# 4_0__TK040_31pin.net
KiCad netlist of a schematic drawn in Altium Designer
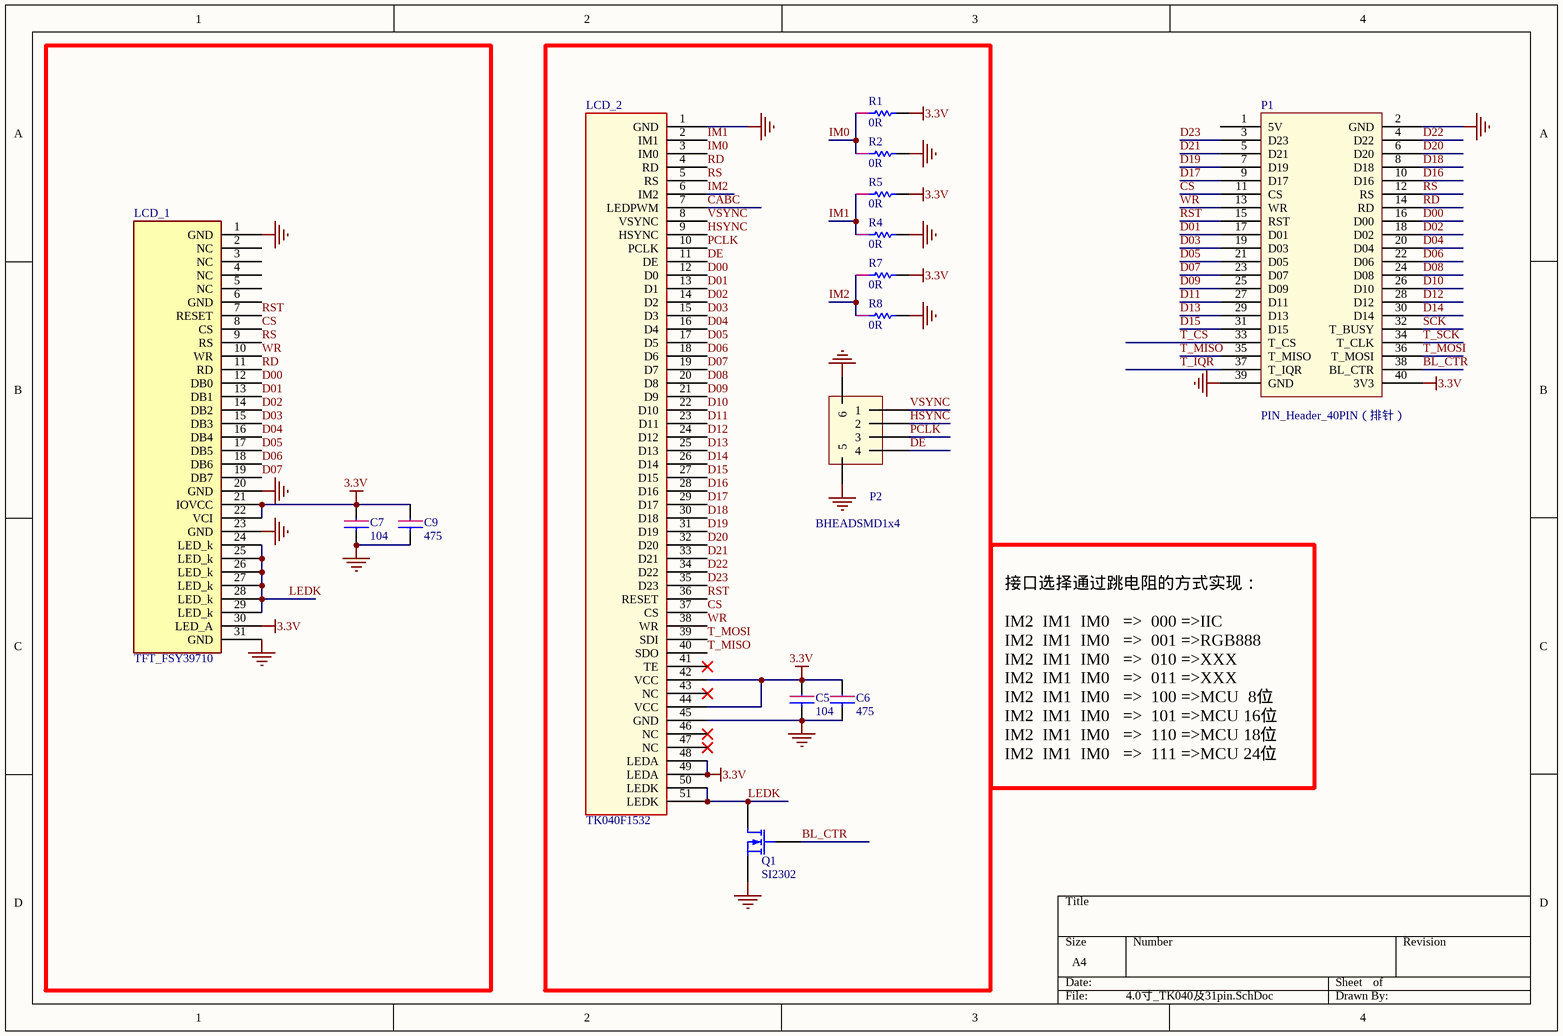
[diagram p0: 4.0寸_TK040及31pin.SchDoc]

(export (version "E")
  (design (tool "Eeschema 10.0.6"))
  (components
    (comp (ref "C5") (value "104") (footprint "C0603-1") (libsource (lib "Tiky") (part "cap")))
    (comp (ref "C6") (value "475") (footprint "C0603-2") (libsource (lib "Tiky") (part "cap")))
    (comp (ref "C7") (value "104") (footprint "C0603-1") (libsource (lib "Tiky") (part "cap")))
    (comp (ref "C9") (value "475") (footprint "C0603-1") (libsource (lib "Tiky") (part "cap")))
    (comp (ref "LCD_1")
      (value "TFT_FSY39710")
      (footprint "TFT_FSY39710")
      (libsource (lib "Tiky") (part "TFT_FSY39710"))
    )
    (comp (ref "LCD_2")
      (value "TK040F1532")
      (footprint "TK040F1532")
      (libsource (lib "Tiky") (part "TK040F1532"))
    )
    (comp (ref "P1")
      (value "PIN_Header_40PIN（排针）")
      (footprint "P_Head_2x20")
      (libsource (lib "Tiky") (part "PIN_Header_40PIN"))
    )
    (comp (ref "P2")
      (value "BHEADSMD1x4")
      (footprint "BHEADSMD1x4")
      (libsource (lib "Tiky") (part "BHEADSMD1x4"))
    )
    (comp (ref "Q1") (value "SI2302") (footprint "SOT23A") (libsource (lib "Tiky") (part "MOSFET-N")))
    (comp (ref "R1") (value "0R") (footprint "R0603") (libsource (lib "Tiky") (part "Resistor")))
    (comp (ref "R2") (value "0R") (footprint "R0603") (libsource (lib "Tiky") (part "Resistor")))
    (comp (ref "R4") (value "0R") (footprint "R0603") (libsource (lib "Tiky") (part "Resistor")))
    (comp (ref "R5") (value "0R") (footprint "R0603") (libsource (lib "Tiky") (part "Resistor")))
    (comp (ref "R7") (value "0R") (footprint "R0603") (libsource (lib "Tiky") (part "Resistor")))
    (comp (ref "R8") (value "0R") (footprint "R0603") (libsource (lib "Tiky") (part "Resistor")))
  )
  (nets
    (net (code "1") (name "/BL_CTR") (class "Default")
      (node (ref "P1") (pin "38") (pinfunction "BL_CTR_38") (pintype "passive"))
      (node (ref "Q1") (pin "1") (pinfunction "G_1") (pintype "passive"))
    )
    (net (code "2") (name "/CABC") (class "Default")
      (node (ref "LCD_2") (pin "7") (pinfunction "LEDPWM_7") (pintype "passive"))
    )
    (net (code "3") (name "/CS") (class "Default")
      (node (ref "LCD_1") (pin "8") (pinfunction "CS_8") (pintype "passive"))
      (node (ref "LCD_2") (pin "37") (pinfunction "CS_37") (pintype "passive"))
      (node (ref "P1") (pin "11") (pinfunction "CS_11") (pintype "passive"))
    )
    (net (code "4") (name "/D00") (class "Default")
      (node (ref "LCD_1") (pin "12") (pinfunction "DB0_12") (pintype "passive"))
      (node (ref "LCD_2") (pin "12") (pinfunction "D0_12") (pintype "passive"))
      (node (ref "P1") (pin "16") (pinfunction "D00_16") (pintype "passive"))
    )
    (net (code "5") (name "/D01") (class "Default")
      (node (ref "LCD_1") (pin "13") (pinfunction "DB1_13") (pintype "passive"))
      (node (ref "LCD_2") (pin "13") (pinfunction "D1_13") (pintype "passive"))
      (node (ref "P1") (pin "17") (pinfunction "D01_17") (pintype "passive"))
    )
    (net (code "6") (name "/D02") (class "Default")
      (node (ref "LCD_1") (pin "14") (pinfunction "DB2_14") (pintype "passive"))
      (node (ref "LCD_2") (pin "14") (pinfunction "D2_14") (pintype "passive"))
      (node (ref "P1") (pin "18") (pinfunction "D02_18") (pintype "passive"))
    )
    (net (code "7") (name "/D03") (class "Default")
      (node (ref "LCD_1") (pin "15") (pinfunction "DB3_15") (pintype "passive"))
      (node (ref "LCD_2") (pin "15") (pinfunction "D3_15") (pintype "passive"))
      (node (ref "P1") (pin "19") (pinfunction "D03_19") (pintype "passive"))
    )
    (net (code "8") (name "/D04") (class "Default")
      (node (ref "LCD_1") (pin "16") (pinfunction "DB4_16") (pintype "passive"))
      (node (ref "LCD_2") (pin "16") (pinfunction "D4_16") (pintype "passive"))
      (node (ref "P1") (pin "20") (pinfunction "D04_20") (pintype "passive"))
    )
    (net (code "9") (name "/D05") (class "Default")
      (node (ref "LCD_1") (pin "17") (pinfunction "DB5_17") (pintype "passive"))
      (node (ref "LCD_2") (pin "17") (pinfunction "D5_17") (pintype "passive"))
      (node (ref "P1") (pin "21") (pinfunction "D05_21") (pintype "passive"))
    )
    (net (code "10") (name "/D06") (class "Default")
      (node (ref "LCD_1") (pin "18") (pinfunction "DB6_18") (pintype "passive"))
      (node (ref "LCD_2") (pin "18") (pinfunction "D6_18") (pintype "passive"))
      (node (ref "P1") (pin "22") (pinfunction "D06_22") (pintype "passive"))
    )
    (net (code "11") (name "/D07") (class "Default")
      (node (ref "LCD_1") (pin "19") (pinfunction "DB7_19") (pintype "passive"))
      (node (ref "LCD_2") (pin "19") (pinfunction "D7_19") (pintype "passive"))
      (node (ref "P1") (pin "23") (pinfunction "D07_23") (pintype "passive"))
    )
    (net (code "12") (name "/D08") (class "Default")
      (node (ref "LCD_2") (pin "20") (pinfunction "D8_20") (pintype "passive"))
      (node (ref "P1") (pin "24") (pinfunction "D08_24") (pintype "passive"))
    )
    (net (code "13") (name "/D09") (class "Default")
      (node (ref "LCD_2") (pin "21") (pinfunction "D9_21") (pintype "passive"))
      (node (ref "P1") (pin "25") (pinfunction "D09_25") (pintype "passive"))
    )
    (net (code "14") (name "/D10") (class "Default")
      (node (ref "LCD_2") (pin "22") (pinfunction "D10_22") (pintype "passive"))
      (node (ref "P1") (pin "26") (pinfunction "D10_26") (pintype "passive"))
    )
    (net (code "15") (name "/D11") (class "Default")
      (node (ref "LCD_2") (pin "23") (pinfunction "D11_23") (pintype "passive"))
      (node (ref "P1") (pin "27") (pinfunction "D11_27") (pintype "passive"))
    )
    (net (code "16") (name "/D12") (class "Default")
      (node (ref "LCD_2") (pin "24") (pinfunction "D12_24") (pintype "passive"))
      (node (ref "P1") (pin "28") (pinfunction "D12_28") (pintype "passive"))
    )
    (net (code "17") (name "/D13") (class "Default")
      (node (ref "LCD_2") (pin "25") (pinfunction "D13_25") (pintype "passive"))
      (node (ref "P1") (pin "29") (pinfunction "D13_29") (pintype "passive"))
    )
    (net (code "18") (name "/D14") (class "Default")
      (node (ref "LCD_2") (pin "26") (pinfunction "D14_26") (pintype "passive"))
      (node (ref "P1") (pin "30") (pinfunction "D14_30") (pintype "passive"))
    )
    (net (code "19") (name "/D15") (class "Default")
      (node (ref "LCD_2") (pin "27") (pinfunction "D15_27") (pintype "passive"))
      (node (ref "P1") (pin "31") (pinfunction "D15_31") (pintype "passive"))
    )
    (net (code "20") (name "/D16") (class "Default")
      (node (ref "LCD_2") (pin "28") (pinfunction "D16_28") (pintype "passive"))
      (node (ref "P1") (pin "10") (pinfunction "D16_10") (pintype "passive"))
    )
    (net (code "21") (name "/D17") (class "Default")
      (node (ref "LCD_2") (pin "29") (pinfunction "D17_29") (pintype "passive"))
      (node (ref "P1") (pin "9") (pinfunction "D17_9") (pintype "passive"))
    )
    (net (code "22") (name "/D18") (class "Default")
      (node (ref "LCD_2") (pin "30") (pinfunction "D18_30") (pintype "passive"))
      (node (ref "P1") (pin "8") (pinfunction "D18_8") (pintype "passive"))
    )
    (net (code "23") (name "/D19") (class "Default")
      (node (ref "LCD_2") (pin "31") (pinfunction "D19_31") (pintype "passive"))
      (node (ref "P1") (pin "7") (pinfunction "D19_7") (pintype "passive"))
    )
    (net (code "24") (name "/D20") (class "Default")
      (node (ref "LCD_2") (pin "32") (pinfunction "D20_32") (pintype "passive"))
      (node (ref "P1") (pin "6") (pinfunction "D20_6") (pintype "passive"))
    )
    (net (code "25") (name "/D21") (class "Default")
      (node (ref "LCD_2") (pin "33") (pinfunction "D21_33") (pintype "passive"))
      (node (ref "P1") (pin "5") (pinfunction "D21_5") (pintype "passive"))
    )
    (net (code "26") (name "/D22") (class "Default")
      (node (ref "LCD_2") (pin "34") (pinfunction "D22_34") (pintype "passive"))
      (node (ref "P1") (pin "4") (pinfunction "D22_4") (pintype "passive"))
    )
    (net (code "27") (name "/D23") (class "Default")
      (node (ref "LCD_2") (pin "35") (pinfunction "D23_35") (pintype "passive"))
      (node (ref "P1") (pin "3") (pinfunction "D23_3") (pintype "passive"))
    )
    (net (code "28") (name "/DE") (class "Default")
      (node (ref "LCD_2") (pin "11") (pinfunction "DE_11") (pintype "passive"))
      (node (ref "P2") (pin "4") (pinfunction "4_4") (pintype "passive"))
    )
    (net (code "29") (name "/HSYNC") (class "Default")
      (node (ref "LCD_2") (pin "9") (pinfunction "HSYNC_9") (pintype "passive"))
      (node (ref "P2") (pin "2") (pinfunction "2_2") (pintype "passive"))
    )
    (net (code "30") (name "/IM0") (class "Default")
      (node (ref "LCD_2") (pin "3") (pinfunction "IM0_3") (pintype "passive"))
      (node (ref "R1") (pin "1") (pinfunction "1_1") (pintype "passive"))
      (node (ref "R2") (pin "1") (pinfunction "1_1") (pintype "passive"))
    )
    (net (code "31") (name "/IM1") (class "Default")
      (node (ref "LCD_2") (pin "2") (pinfunction "IM1_2") (pintype "passive"))
      (node (ref "R4") (pin "1") (pinfunction "1_1") (pintype "passive"))
      (node (ref "R5") (pin "1") (pinfunction "1_1") (pintype "passive"))
    )
    (net (code "32") (name "/IM2") (class "Default")
      (node (ref "LCD_2") (pin "6") (pinfunction "IM2_6") (pintype "passive"))
      (node (ref "R7") (pin "1") (pinfunction "1_1") (pintype "passive"))
      (node (ref "R8") (pin "1") (pinfunction "1_1") (pintype "passive"))
    )
    (net (code "33") (name "/LEDK") (class "Default")
      (node (ref "LCD_1") (pin "24") (pinfunction "LED_k_24") (pintype "passive"))
      (node (ref "LCD_1") (pin "25") (pinfunction "LED_k_25") (pintype "passive"))
      (node (ref "LCD_1") (pin "26") (pinfunction "LED_k_26") (pintype "passive"))
      (node (ref "LCD_1") (pin "27") (pinfunction "LED_k_27") (pintype "passive"))
      (node (ref "LCD_1") (pin "28") (pinfunction "LED_k_28") (pintype "passive"))
      (node (ref "LCD_1") (pin "29") (pinfunction "LED_k_29") (pintype "passive"))
      (node (ref "LCD_2") (pin "50") (pinfunction "LEDK_50") (pintype "passive"))
      (node (ref "LCD_2") (pin "51") (pinfunction "LEDK_51") (pintype "passive"))
      (node (ref "Q1") (pin "3") (pinfunction "D_3") (pintype "passive"))
    )
    (net (code "34") (name "/PCLK") (class "Default")
      (node (ref "LCD_2") (pin "10") (pinfunction "PCLK_10") (pintype "passive"))
      (node (ref "P2") (pin "3") (pinfunction "3_3") (pintype "passive"))
    )
    (net (code "35") (name "/RD") (class "Default")
      (node (ref "LCD_1") (pin "11") (pinfunction "RD_11") (pintype "passive"))
      (node (ref "LCD_2") (pin "4") (pinfunction "RD_4") (pintype "passive"))
      (node (ref "P1") (pin "14") (pinfunction "RD_14") (pintype "passive"))
    )
    (net (code "36") (name "/RS") (class "Default")
      (node (ref "LCD_1") (pin "9") (pinfunction "RS_9") (pintype "passive"))
      (node (ref "LCD_2") (pin "5") (pinfunction "RS_5") (pintype "passive"))
      (node (ref "P1") (pin "12") (pinfunction "RS_12") (pintype "passive"))
    )
    (net (code "37") (name "/RST") (class "Default")
      (node (ref "LCD_1") (pin "7") (pinfunction "RESET_7") (pintype "passive"))
      (node (ref "LCD_2") (pin "36") (pinfunction "RESET_36") (pintype "passive"))
      (node (ref "P1") (pin "15") (pinfunction "RST_15") (pintype "passive"))
    )
    (net (code "38") (name "/SCK") (class "Default")
      (node (ref "P1") (pin "32") (pinfunction "T_BUSY_32") (pintype "passive"))
    )
    (net (code "39") (name "/T_CS") (class "Default")
      (node (ref "P1") (pin "33") (pinfunction "T_CS_33") (pintype "passive"))
    )
    (net (code "40") (name "/T_IQR") (class "Default")
      (node (ref "P1") (pin "37") (pinfunction "T_IQR_37") (pintype "passive"))
    )
    (net (code "41") (name "/T_MISO") (class "Default")
      (node (ref "LCD_2") (pin "40") (pinfunction "SDO_40") (pintype "passive"))
      (node (ref "P1") (pin "35") (pinfunction "T_MISO_35") (pintype "passive"))
    )
    (net (code "42") (name "/T_MOSI") (class "Default")
      (node (ref "LCD_2") (pin "39") (pinfunction "SDI_39") (pintype "passive"))
      (node (ref "P1") (pin "36") (pinfunction "T_MOSI_36") (pintype "passive"))
    )
    (net (code "43") (name "/T_SCK") (class "Default")
      (node (ref "P1") (pin "34") (pinfunction "T_CLK_34") (pintype "passive"))
    )
    (net (code "44") (name "/VSYNC") (class "Default")
      (node (ref "LCD_2") (pin "8") (pinfunction "VSYNC_8") (pintype "passive"))
      (node (ref "P2") (pin "1") (pinfunction "1_1") (pintype "passive"))
    )
    (net (code "45") (name "/WR") (class "Default")
      (node (ref "LCD_1") (pin "10") (pinfunction "WR_10") (pintype "passive"))
      (node (ref "LCD_2") (pin "38") (pinfunction "WR_38") (pintype "passive"))
      (node (ref "P1") (pin "13") (pinfunction "WR_13") (pintype "passive"))
    )
    (net (code "46") (name "3.3V") (class "Default")
      (node (ref "C5") (pin "1") (pinfunction "1_1") (pintype "passive"))
      (node (ref "C6") (pin "1") (pinfunction "1_1") (pintype "passive"))
      (node (ref "C7") (pin "1") (pinfunction "1_1") (pintype "passive"))
      (node (ref "C9") (pin "1") (pinfunction "1_1") (pintype "passive"))
      (node (ref "LCD_1") (pin "21") (pinfunction "IOVCC_21") (pintype "passive"))
      (node (ref "LCD_1") (pin "22") (pinfunction "VCI_22") (pintype "passive"))
      (node (ref "LCD_1") (pin "30") (pinfunction "LED_A_30") (pintype "passive"))
      (node (ref "LCD_2") (pin "42") (pinfunction "VCC_42") (pintype "passive"))
      (node (ref "LCD_2") (pin "44") (pinfunction "VCC_44") (pintype "passive"))
      (node (ref "LCD_2") (pin "48") (pinfunction "LEDA_48") (pintype "passive"))
      (node (ref "LCD_2") (pin "49") (pinfunction "LEDA_49") (pintype "passive"))
      (node (ref "P1") (pin "40") (pinfunction "3V3_40") (pintype "passive"))
      (node (ref "R1") (pin "2") (pinfunction "2_2") (pintype "passive"))
      (node (ref "R5") (pin "2") (pinfunction "2_2") (pintype "passive"))
      (node (ref "R7") (pin "2") (pinfunction "2_2") (pintype "passive"))
    )
    (net (code "47") (name "GND") (class "Default")
      (node (ref "C5") (pin "2") (pinfunction "2_2") (pintype "passive"))
      (node (ref "C6") (pin "2") (pinfunction "2_2") (pintype "passive"))
      (node (ref "C7") (pin "2") (pinfunction "2_2") (pintype "passive"))
      (node (ref "C9") (pin "2") (pinfunction "2_2") (pintype "passive"))
      (node (ref "LCD_1") (pin "1") (pinfunction "GND_1") (pintype "passive"))
      (node (ref "LCD_1") (pin "20") (pinfunction "GND_20") (pintype "passive"))
      (node (ref "LCD_1") (pin "23") (pinfunction "GND_23") (pintype "passive"))
      (node (ref "LCD_1") (pin "31") (pinfunction "GND_31") (pintype "passive"))
      (node (ref "LCD_2") (pin "1") (pinfunction "GND_1") (pintype "passive"))
      (node (ref "LCD_2") (pin "45") (pinfunction "GND_45") (pintype "passive"))
      (node (ref "P1") (pin "2") (pinfunction "GND_2") (pintype "passive"))
      (node (ref "P1") (pin "39") (pinfunction "GND_39") (pintype "passive"))
      (node (ref "P2") (pin "5") (pinfunction "5_5") (pintype "passive"))
      (node (ref "P2") (pin "6") (pinfunction "6_6") (pintype "passive"))
      (node (ref "Q1") (pin "2") (pinfunction "S_2") (pintype "passive"))
      (node (ref "R2") (pin "2") (pinfunction "2_2") (pintype "passive"))
      (node (ref "R4") (pin "2") (pinfunction "2_2") (pintype "passive"))
      (node (ref "R8") (pin "2") (pinfunction "2_2") (pintype "passive"))
    )
    (net (code "48") (name "unconnected-(LCD_1-GND-Pad6)") (class "Default")
      (node (ref "LCD_1") (pin "6") (pinfunction "GND_6") (pintype "passive"))
    )
    (net (code "49") (name "unconnected-(LCD_1-NC-Pad2)") (class "Default")
      (node (ref "LCD_1") (pin "2") (pinfunction "NC_2") (pintype "passive"))
    )
    (net (code "50") (name "unconnected-(LCD_1-NC-Pad3)") (class "Default")
      (node (ref "LCD_1") (pin "3") (pinfunction "NC_3") (pintype "passive"))
    )
    (net (code "51") (name "unconnected-(LCD_1-NC-Pad4)") (class "Default")
      (node (ref "LCD_1") (pin "4") (pinfunction "NC_4") (pintype "passive"))
    )
    (net (code "52") (name "unconnected-(LCD_1-NC-Pad5)") (class "Default")
      (node (ref "LCD_1") (pin "5") (pinfunction "NC_5") (pintype "passive"))
    )
    (net (code "53") (name "unconnected-(LCD_2-NC-Pad43)") (class "Default")
      (node (ref "LCD_2") (pin "43") (pinfunction "NC_43") (pintype "passive+no_connect"))
    )
    (net (code "54") (name "unconnected-(LCD_2-NC-Pad46)") (class "Default")
      (node (ref "LCD_2") (pin "46") (pinfunction "NC_46") (pintype "passive+no_connect"))
    )
    (net (code "55") (name "unconnected-(LCD_2-NC-Pad47)") (class "Default")
      (node (ref "LCD_2") (pin "47") (pinfunction "NC_47") (pintype "passive+no_connect"))
    )
    (net (code "56") (name "unconnected-(LCD_2-TE-Pad41)") (class "Default")
      (node (ref "LCD_2") (pin "41") (pinfunction "TE_41") (pintype "passive+no_connect"))
    )
    (net (code "57") (name "unconnected-(P1-5V-Pad1)") (class "Default")
      (node (ref "P1") (pin "1") (pinfunction "5V_1") (pintype "passive"))
    )
  )
)
